# microcontroller.net
KiCad netlist of a schematic drawn in Altium Designer
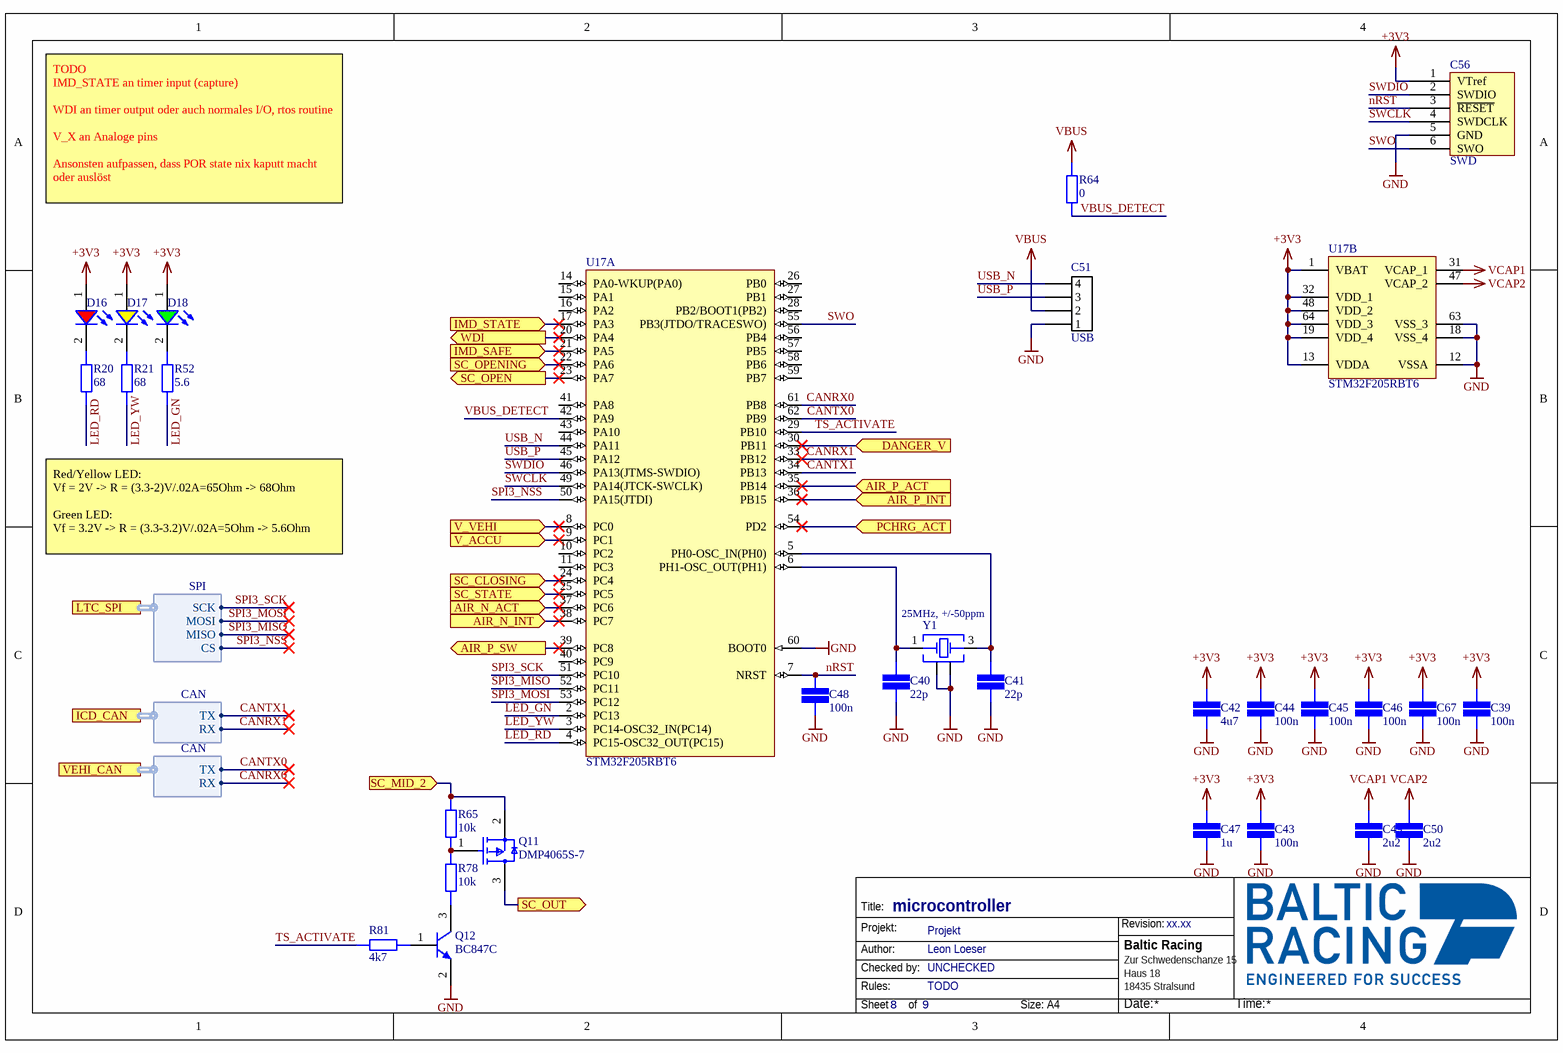
[diagram p0: microcontroller.SchDoc]

(export (version "E")
  (design (tool "Eeschema 10.0.6"))
  (components
    (comp (ref "C39")
      (value "100n")
      (footprint "CAP 0603/1608")
      (description "Capacitor with multiple Footprints")
      (fields (field (name "VOLTAGE") "6.3V") (field (name "Comment") "SMD Capacitor"))
      (libsource (lib "Standardbauteile") (part "SMD Capacitor"))
    )
    (comp (ref "C40")
      (value "22p")
      (footprint "CAP 0603/1608")
      (description "Capacitor with multiple Footprints")
      (fields (field (name "VOLTAGE") "6.3V") (field (name "Comment") "SMD Capacitor"))
      (libsource (lib "") (part "SMD Capacitor_1"))
    )
    (comp (ref "C41")
      (value "22p")
      (footprint "CAP 0603/1608")
      (description "Capacitor with multiple Footprints")
      (fields (field (name "VOLTAGE") "6.3V") (field (name "Comment") "SMD Capacitor"))
      (libsource (lib "") (part "SMD Capacitor_1"))
    )
    (comp (ref "C42")
      (value "4u7")
      (footprint "CAP 0805/2012")
      (description "Capacitor with multiple Footprints")
      (fields (field (name "VOLTAGE") "6.3V") (field (name "Comment") "SMD Capacitor"))
      (libsource (lib "Standardbauteile") (part "SMD Capacitor"))
    )
    (comp (ref "C43")
      (value "100n")
      (footprint "CAP 0603/1608")
      (description "Capacitor with multiple Footprints")
      (fields (field (name "VOLTAGE") "6.3V") (field (name "Comment") "SMD Capacitor"))
      (libsource (lib "Standardbauteile") (part "SMD Capacitor"))
    )
    (comp (ref "C44")
      (value "100n")
      (footprint "CAP 0603/1608")
      (description "Capacitor with multiple Footprints")
      (fields (field (name "VOLTAGE") "6.3V") (field (name "Comment") "SMD Capacitor"))
      (libsource (lib "Standardbauteile") (part "SMD Capacitor"))
    )
    (comp (ref "C45")
      (value "100n")
      (footprint "CAP 0603/1608")
      (description "Capacitor with multiple Footprints")
      (fields (field (name "VOLTAGE") "6.3V") (field (name "Comment") "SMD Capacitor"))
      (libsource (lib "Standardbauteile") (part "SMD Capacitor"))
    )
    (comp (ref "C46")
      (value "100n")
      (footprint "CAP 0603/1608")
      (description "Capacitor with multiple Footprints")
      (fields (field (name "VOLTAGE") "6.3V") (field (name "Comment") "SMD Capacitor"))
      (libsource (lib "Standardbauteile") (part "SMD Capacitor"))
    )
    (comp (ref "C47")
      (value "1u")
      (footprint "CAP 0805/2012")
      (description "Capacitor with multiple Footprints")
      (fields (field (name "VOLTAGE") "6.3V") (field (name "Comment") "SMD Capacitor"))
      (libsource (lib "Standardbauteile") (part "SMD Capacitor"))
    )
    (comp (ref "C48")
      (value "100n")
      (footprint "CAP 0603/1608")
      (description "Capacitor with multiple Footprints")
      (fields (field (name "VOLTAGE") "6.3V") (field (name "Comment") "SMD Capacitor"))
      (libsource (lib "Standardbauteile") (part "SMD Capacitor"))
    )
    (comp (ref "C49")
      (value "2u2")
      (footprint "CAP 0805/2012")
      (description "Capacitor with multiple Footprints")
      (fields (field (name "VOLTAGE") "6.3V") (field (name "Comment") "SMD Capacitor"))
      (libsource (lib "Standardbauteile") (part "SMD Capacitor"))
    )
    (comp (ref "C50")
      (value "2u2")
      (footprint "CAP 0805/2012")
      (description "Capacitor with multiple Footprints")
      (fields (field (name "VOLTAGE") "6.3V") (field (name "Comment") "SMD Capacitor"))
      (libsource (lib "Standardbauteile") (part "SMD Capacitor"))
    )
    (comp (ref "C51")
      (value "USB")
      (footprint "43045-0412")
      (description "Molex Micro-Fit 3.0 4-Pin\r\n600V\r\n8.5V")
      (libsource (lib "Standardbauteile") (part "MicroFit3.0 4-Pin"))
    )
    (comp (ref "C56")
      (value "SWD")
      (footprint "SEGGER_6_PIN")
      (libsource (lib "Standardbauteile") (part "Segger 6-Pin"))
    )
    (comp (ref "C67")
      (value "100n")
      (footprint "CAP 0603/1608")
      (description "Capacitor with multiple Footprints")
      (fields (field (name "VOLTAGE") "6.3V") (field (name "Comment") "SMD Capacitor"))
      (libsource (lib "Standardbauteile") (part "SMD Capacitor"))
    )
    (comp (ref "D16")
      (value "Red, 2 V, 140 deg")
      (footprint "WL-SMCW_0603_H=0.25")
      (description "SMT Mono-color Chip LED Waterclear WL-SMCW, size 0603, Red, 2 V, 140 deg, 100 mcd")
      (fields (field (name "PART NUMBER") "150060RS75020") (field (name "PUBLISHER") "Wurth Elektronik"))
      (libsource (lib "ALTIUM-WL-SMCW-rev18c") (part "150060RS75020"))
    )
    (comp (ref "D17")
      (value "Yellow, 2 V, 140 deg")
      (footprint "WL-SMCW_0603_H=0.25")
      (description "SMT Mono-color Chip LED Waterclear WL-SMCW, size 0603, Yellow, 2 V, 140 deg, 130 mcd")
      (fields (field (name "PART NUMBER") "150060YS75020") (field (name "PUBLISHER") "Wurth Elektronik"))
      (libsource (lib "ALTIUM-WL-SMCW-rev18c") (part "150060YS75020"))
    )
    (comp (ref "D18")
      (value "Green, 3.2 V, 140 deg")
      (footprint "WL-SMCW_0603_H=0.25")
      (description "SMT Mono-color Chip LED Waterclear WL-SMCW, size 0603, Green, 3.2 V, 140 deg, 700 mcd")
      (fields (field (name "PART NUMBER") "150060GS75020") (field (name "PUBLISHER") "Wurth Elektronik"))
      (libsource (lib "ALTIUM-WL-SMCW-rev18c") (part "150060GS75020"))
    )
    (comp (ref "Q11")
      (value "DMP4065S-7")
      (footprint "FP-SOT23-MFG")
      (description "MOSFET P-CH 40V 2.4A SOT23")
      (fields
        (field (name "MANUFACTURER") "Diodes Inc.")
        (field (name "OCTOPART") "https://octopart.com/dmp4065s-7-diodes+inc.-57605044")
      )
      (libsource (lib "Altium Content Vault") (part "90d26376f95f59a583a7107ec0b7fdb"))
    )
    (comp (ref "Q12")
      (value "BC847C")
      (footprint "INF-SOT23_L")
      (description "NPN Silicon AF Transistor, 45 V VCEO, 100 mA IC, SOT23, Reel, Green")
      (fields (field (name "MANUFACTURER") "Infineon"))
      (libsource (lib "Altium Content Vault") (part "INF-BJTNPN-BEC-3"))
    )
    (comp (ref "R20")
      (value "68")
      (footprint "STACKPOLE CSR0603")
      (description "Resistor with multiple footprints")
      (fields (field (name "Comment") "SMD Resistor"))
      (libsource (lib "Standardbauteile") (part "SMD Resistor"))
    )
    (comp (ref "R21")
      (value "68")
      (footprint "STACKPOLE CSR0603")
      (description "Resistor with multiple footprints")
      (fields (field (name "Comment") "SMD Resistor"))
      (libsource (lib "Standardbauteile") (part "SMD Resistor"))
    )
    (comp (ref "R52")
      (value "5.6")
      (footprint "STACKPOLE CSR0603")
      (description "Resistor with multiple footprints")
      (fields (field (name "Comment") "SMD Resistor"))
      (libsource (lib "Standardbauteile") (part "SMD Resistor"))
    )
    (comp (ref "R64")
      (value "0")
      (footprint "STACKPOLE CSR0603")
      (description "Resistor with multiple footprints")
      (fields (field (name "Comment") "SMD Resistor"))
      (libsource (lib "Standardbauteile") (part "SMD Resistor"))
    )
    (comp (ref "R65")
      (value "10k")
      (footprint "STACKPOLE CSR0603")
      (description "Resistor with multiple footprints")
      (fields (field (name "Comment") "SMD Resistor"))
      (libsource (lib "Standardbauteile") (part "SMD Resistor"))
    )
    (comp (ref "R78")
      (value "10k")
      (footprint "STACKPOLE CSR0603")
      (description "Resistor with multiple footprints")
      (fields (field (name "Comment") "SMD Resistor"))
      (libsource (lib "Standardbauteile") (part "SMD Resistor"))
    )
    (comp (ref "R81")
      (value "4k7")
      (footprint "STACKPOLE CSR0603")
      (description "Resistor with multiple footprints")
      (fields (field (name "Comment") "SMD Resistor"))
      (libsource (lib "Standardbauteile") (part "SMD Resistor"))
    )
    (comp (ref "U17")
      (value "STM32F205RBT6")
      (footprint "STM-LQFP64_L")
      (libsource (lib "Altium Content Vault") (part "MC-ARM-STM32F20X-SQ64"))
    )
    (comp (ref "Y1")
      (value "25MHz, +/-50ppm")
      (footprint "WE-XTAL_CFPX-180")
      (description "WE-XTAL Quartz Crystal, SMT, CFPX-180, 25MHz, +/-50ppm")
      (fields (field (name "PART NUMBER") "830035268") (field (name "PUBLISHER") "Wurth Elektronik"))
      (libsource (lib "Altium_WE-XTAL_rev19c") (part "830035268"))
    )
  )
  (nets
    (net (code "3") (name "+3V3") (class "Default")
      (node (ref "C39") (pin "2") (pinfunction "2_2") (pintype "passive"))
      (node (ref "C42") (pin "2") (pinfunction "2_2") (pintype "passive"))
      (node (ref "C43") (pin "2") (pinfunction "2_2") (pintype "passive"))
      (node (ref "C44") (pin "2") (pinfunction "2_2") (pintype "passive"))
      (node (ref "C45") (pin "2") (pinfunction "2_2") (pintype "passive"))
      (node (ref "C46") (pin "2") (pinfunction "2_2") (pintype "passive"))
      (node (ref "C47") (pin "2") (pinfunction "2_2") (pintype "passive"))
      (node (ref "C56") (pin "1") (pinfunction "VTref_1") (pintype "passive"))
      (node (ref "C67") (pin "2") (pinfunction "2_2") (pintype "passive"))
      (node (ref "D16") (pin "1") (pinfunction "A_1") (pintype "passive"))
      (node (ref "D17") (pin "1") (pinfunction "A_1") (pintype "passive"))
      (node (ref "D18") (pin "1") (pinfunction "A_1") (pintype "passive"))
      (node (ref "U17") (pin "1") (pinfunction "VBAT_1") (pintype "power_in"))
      (node (ref "U17") (pin "13") (pinfunction "VDDA_13") (pintype "power_in"))
      (node (ref "U17") (pin "19") (pinfunction "VDD_4_19") (pintype "power_in"))
      (node (ref "U17") (pin "32") (pinfunction "VDD_1_32") (pintype "power_in"))
      (node (ref "U17") (pin "48") (pinfunction "VDD_2_48") (pintype "power_in"))
      (node (ref "U17") (pin "64") (pinfunction "VDD_3_64") (pintype "power_in"))
    )
    (net (code "4") (name "/AIR_N_ACT") (class "Default")
      (node (ref "U17") (pin "37") (pinfunction "PC6_37") (pintype "bidirectional+no_connect"))
    )
    (net (code "5") (name "/AIR_N_INT") (class "Default")
      (node (ref "U17") (pin "38") (pinfunction "PC7_38") (pintype "bidirectional+no_connect"))
    )
    (net (code "6") (name "/AIR_P_ACT") (class "Default")
      (node (ref "U17") (pin "35") (pinfunction "PB14_35") (pintype "bidirectional+no_connect"))
    )
    (net (code "7") (name "/AIR_P_INT") (class "Default")
      (node (ref "U17") (pin "36") (pinfunction "PB15_36") (pintype "bidirectional+no_connect"))
    )
    (net (code "8") (name "/AIR_P_SW") (class "Default")
      (node (ref "U17") (pin "39") (pinfunction "PC8_39") (pintype "bidirectional+no_connect"))
    )
    (net (code "9") (name "/CANRX0") (class "Default")
      (node (ref "U17") (pin "61") (pinfunction "PB8_61") (pintype "bidirectional+no_connect"))
    )
    (net (code "10") (name "/CANRX1") (class "Default")
      (node (ref "U17") (pin "33") (pinfunction "PB12_33") (pintype "bidirectional+no_connect"))
    )
    (net (code "11") (name "/CANTX0") (class "Default")
      (node (ref "U17") (pin "62") (pinfunction "PB9_62") (pintype "bidirectional+no_connect"))
    )
    (net (code "12") (name "/CANTX1") (class "Default")
      (node (ref "U17") (pin "34") (pinfunction "PB13_34") (pintype "bidirectional+no_connect"))
    )
    (net (code "13") (name "/DANGER_V") (class "Default")
      (node (ref "U17") (pin "30") (pinfunction "PB11_30") (pintype "bidirectional+no_connect"))
    )
    (net (code "14") (name "/IMD_SAFE") (class "Default")
      (node (ref "U17") (pin "21") (pinfunction "PA5_21") (pintype "bidirectional+no_connect"))
    )
    (net (code "15") (name "/IMD_STATE") (class "Default")
      (node (ref "U17") (pin "17") (pinfunction "PA3_17") (pintype "bidirectional+no_connect"))
    )
    (net (code "16") (name "/LED_GN") (class "Default")
      (node (ref "R52") (pin "1") (pinfunction "1_1") (pintype "passive"))
      (node (ref "U17") (pin "2") (pinfunction "PC13_2") (pintype "bidirectional"))
    )
    (net (code "17") (name "/LED_RD") (class "Default")
      (node (ref "R20") (pin "1") (pinfunction "1_1") (pintype "passive"))
      (node (ref "U17") (pin "4") (pinfunction "PC15-OSC32_OUT(PC15)_4") (pintype "bidirectional"))
    )
    (net (code "18") (name "/LED_YW") (class "Default")
      (node (ref "R21") (pin "1") (pinfunction "1_1") (pintype "passive"))
      (node (ref "U17") (pin "3") (pinfunction "PC14-OSC32_IN(PC14)_3") (pintype "bidirectional"))
    )
    (net (code "19") (name "/PCHRG_ACT") (class "Default")
      (node (ref "U17") (pin "54") (pinfunction "PD2_54") (pintype "bidirectional+no_connect"))
    )
    (net (code "20") (name "/SC_CLOSING") (class "Default")
      (node (ref "U17") (pin "24") (pinfunction "PC4_24") (pintype "bidirectional+no_connect"))
    )
    (net (code "21") (name "/SC_MID_2") (class "Default")
      (node (ref "Q11") (pin "2") (pinfunction "S_2") (pintype "passive"))
      (node (ref "R65") (pin "1") (pinfunction "1_1") (pintype "passive"))
    )
    (net (code "22") (name "/SC_OPEN") (class "Default")
      (node (ref "U17") (pin "23") (pinfunction "PA7_23") (pintype "bidirectional+no_connect"))
    )
    (net (code "23") (name "/SC_OPENING") (class "Default")
      (node (ref "U17") (pin "22") (pinfunction "PA6_22") (pintype "bidirectional+no_connect"))
    )
    (net (code "24") (name "/SC_OUT") (class "Default")
      (node (ref "Q11") (pin "3") (pinfunction "D_3") (pintype "passive"))
    )
    (net (code "25") (name "/SC_STATE") (class "Default")
      (node (ref "U17") (pin "25") (pinfunction "PC5_25") (pintype "bidirectional+no_connect"))
    )
    (net (code "26") (name "/SPI3_MISO") (class "Default")
      (node (ref "U17") (pin "52") (pinfunction "PC11_52") (pintype "bidirectional+no_connect"))
    )
    (net (code "27") (name "/SPI3_MOSI") (class "Default")
      (node (ref "U17") (pin "53") (pinfunction "PC12_53") (pintype "bidirectional+no_connect"))
    )
    (net (code "28") (name "/SPI3_NSS") (class "Default")
      (node (ref "U17") (pin "50") (pinfunction "PA15(JTDI)_50") (pintype "bidirectional+no_connect"))
    )
    (net (code "29") (name "/SPI3_SCK") (class "Default")
      (node (ref "U17") (pin "51") (pinfunction "PC10_51") (pintype "bidirectional+no_connect"))
    )
    (net (code "30") (name "/SWCLK") (class "Default")
      (node (ref "C56") (pin "4") (pinfunction "SWDCLK_4") (pintype "passive"))
      (node (ref "U17") (pin "49") (pinfunction "PA14(JTCK-SWCLK)_49") (pintype "bidirectional"))
    )
    (net (code "31") (name "/SWDIO") (class "Default")
      (node (ref "C56") (pin "2") (pinfunction "SWDIO_2") (pintype "passive"))
      (node (ref "U17") (pin "46") (pinfunction "PA13(JTMS-SWDIO)_46") (pintype "bidirectional"))
    )
    (net (code "32") (name "/SWO") (class "Default")
      (node (ref "C56") (pin "6") (pinfunction "SWO_6") (pintype "passive"))
      (node (ref "U17") (pin "55") (pinfunction "PB3(JTDO/TRACESWO)_55") (pintype "bidirectional"))
    )
    (net (code "33") (name "/TS_ACTIVATE") (class "Default")
      (node (ref "R81") (pin "2") (pinfunction "2_2") (pintype "passive"))
      (node (ref "U17") (pin "29") (pinfunction "PB10_29") (pintype "bidirectional"))
    )
    (net (code "34") (name "/USB_N") (class "Default")
      (node (ref "C51") (pin "4") (pinfunction "4_4") (pintype "passive"))
      (node (ref "U17") (pin "44") (pinfunction "PA11_44") (pintype "bidirectional"))
    )
    (net (code "35") (name "/USB_P") (class "Default")
      (node (ref "C51") (pin "3") (pinfunction "3_3") (pintype "passive"))
      (node (ref "U17") (pin "45") (pinfunction "PA12_45") (pintype "bidirectional"))
    )
    (net (code "36") (name "/VBUS_DETECT") (class "Default")
      (node (ref "R64") (pin "1") (pinfunction "1_1") (pintype "passive"))
      (node (ref "U17") (pin "42") (pinfunction "PA9_42") (pintype "bidirectional"))
    )
    (net (code "37") (name "/V_ACCU") (class "Default")
      (node (ref "U17") (pin "9") (pinfunction "PC1_9") (pintype "bidirectional+no_connect"))
    )
    (net (code "38") (name "/V_VEHI") (class "Default")
      (node (ref "U17") (pin "8") (pinfunction "PC0_8") (pintype "bidirectional+no_connect"))
    )
    (net (code "39") (name "/WDI") (class "Default")
      (node (ref "U17") (pin "20") (pinfunction "PA4_20") (pintype "bidirectional+no_connect"))
    )
    (net (code "40") (name "/nRST") (class "Default")
      (node (ref "C48") (pin "2") (pinfunction "2_2") (pintype "passive"))
      (node (ref "C56") (pin "3") (pinfunction "~{RESET}_3") (pintype "passive"))
      (node (ref "U17") (pin "7") (pinfunction "NRST_7") (pintype "bidirectional"))
    )
    (net (code "43") (name "GND") (class "Default")
      (node (ref "C39") (pin "1") (pinfunction "1_1") (pintype "passive"))
      (node (ref "C40") (pin "1") (pinfunction "1_1") (pintype "passive"))
      (node (ref "C41") (pin "1") (pinfunction "1_1") (pintype "passive"))
      (node (ref "C42") (pin "1") (pinfunction "1_1") (pintype "passive"))
      (node (ref "C43") (pin "1") (pinfunction "1_1") (pintype "passive"))
      (node (ref "C44") (pin "1") (pinfunction "1_1") (pintype "passive"))
      (node (ref "C45") (pin "1") (pinfunction "1_1") (pintype "passive"))
      (node (ref "C46") (pin "1") (pinfunction "1_1") (pintype "passive"))
      (node (ref "C47") (pin "1") (pinfunction "1_1") (pintype "passive"))
      (node (ref "C48") (pin "1") (pinfunction "1_1") (pintype "passive"))
      (node (ref "C49") (pin "1") (pinfunction "1_1") (pintype "passive"))
      (node (ref "C50") (pin "1") (pinfunction "1_1") (pintype "passive"))
      (node (ref "C51") (pin "1") (pinfunction "1_1") (pintype "passive"))
      (node (ref "C56") (pin "5") (pinfunction "GND_5") (pintype "passive"))
      (node (ref "C67") (pin "1") (pinfunction "1_1") (pintype "passive"))
      (node (ref "Q12") (pin "2") (pinfunction "E_2") (pintype "passive"))
      (node (ref "U17") (pin "12") (pinfunction "VSSA_12") (pintype "power_in"))
      (node (ref "U17") (pin "18") (pinfunction "VSS_4_18") (pintype "power_in"))
      (node (ref "U17") (pin "60") (pinfunction "BOOT0_60") (pintype "input"))
      (node (ref "U17") (pin "63") (pinfunction "VSS_3_63") (pintype "power_in"))
      (node (ref "Y1") (pin "2") (pinfunction "GND_2") (pintype "passive"))
      (node (ref "Y1") (pin "4") (pinfunction "GND_4") (pintype "passive"))
    )
    (net (code "44") (name "Net-(D16-K)") (class "Default")
      (node (ref "D16") (pin "2") (pinfunction "K_2") (pintype "passive"))
      (node (ref "R20") (pin "2") (pinfunction "2_2") (pintype "passive"))
    )
    (net (code "45") (name "Net-(D17-K)") (class "Default")
      (node (ref "D17") (pin "2") (pinfunction "K_2") (pintype "passive"))
      (node (ref "R21") (pin "2") (pinfunction "2_2") (pintype "passive"))
    )
    (net (code "46") (name "Net-(D18-K)") (class "Default")
      (node (ref "D18") (pin "2") (pinfunction "K_2") (pintype "passive"))
      (node (ref "R52") (pin "2") (pinfunction "2_2") (pintype "passive"))
    )
    (net (code "47") (name "Net-(Q11-G)") (class "Default")
      (node (ref "Q11") (pin "1") (pinfunction "G_1") (pintype "passive"))
      (node (ref "R65") (pin "2") (pinfunction "2_2") (pintype "passive"))
      (node (ref "R78") (pin "1") (pinfunction "1_1") (pintype "passive"))
    )
    (net (code "48") (name "Net-(Q12-B)") (class "Default")
      (node (ref "Q12") (pin "1") (pinfunction "B_1") (pintype "passive"))
      (node (ref "R81") (pin "1") (pinfunction "1_1") (pintype "passive"))
    )
    (net (code "49") (name "Net-(Q12-C)") (class "Default")
      (node (ref "Q12") (pin "3") (pinfunction "C_3") (pintype "passive"))
      (node (ref "R78") (pin "2") (pinfunction "2_2") (pintype "passive"))
    )
    (net (code "50") (name "Net-(U17A-PH0-OSC_IN(PH0))") (class "Default")
      (node (ref "C41") (pin "2") (pinfunction "2_2") (pintype "passive"))
      (node (ref "U17") (pin "5") (pinfunction "PH0-OSC_IN(PH0)_5") (pintype "bidirectional"))
      (node (ref "Y1") (pin "3") (pinfunction "Crystal_3") (pintype "passive"))
    )
    (net (code "51") (name "Net-(U17A-PH1-OSC_OUT(PH1))") (class "Default")
      (node (ref "C40") (pin "2") (pinfunction "2_2") (pintype "passive"))
      (node (ref "U17") (pin "6") (pinfunction "PH1-OSC_OUT(PH1)_6") (pintype "bidirectional"))
      (node (ref "Y1") (pin "1") (pinfunction "Crystal_1") (pintype "passive"))
    )
    (net (code "52") (name "VBUS") (class "Default")
      (node (ref "C51") (pin "2") (pinfunction "2_2") (pintype "passive"))
      (node (ref "R64") (pin "2") (pinfunction "2_2") (pintype "passive"))
    )
    (net (code "53") (name "VCAP1") (class "Default")
      (node (ref "C49") (pin "2") (pinfunction "2_2") (pintype "passive"))
      (node (ref "U17") (pin "31") (pinfunction "VCAP_1_31") (pintype "power_in"))
    )
    (net (code "54") (name "VCAP2") (class "Default")
      (node (ref "C50") (pin "2") (pinfunction "2_2") (pintype "passive"))
      (node (ref "U17") (pin "47") (pinfunction "VCAP_2_47") (pintype "power_in"))
    )
    (net (code "55") (name "unconnected-(U17A-PA0-WKUP(PA0)-Pad14)") (class "Default")
      (node (ref "U17") (pin "14") (pinfunction "PA0-WKUP(PA0)_14") (pintype "bidirectional"))
    )
    (net (code "56") (name "unconnected-(U17A-PA1-Pad15)") (class "Default")
      (node (ref "U17") (pin "15") (pinfunction "PA1_15") (pintype "bidirectional"))
    )
    (net (code "57") (name "unconnected-(U17A-PA2-Pad16)") (class "Default")
      (node (ref "U17") (pin "16") (pinfunction "PA2_16") (pintype "bidirectional"))
    )
    (net (code "58") (name "unconnected-(U17A-PA8-Pad41)") (class "Default")
      (node (ref "U17") (pin "41") (pinfunction "PA8_41") (pintype "bidirectional"))
    )
    (net (code "59") (name "unconnected-(U17A-PA10-Pad43)") (class "Default")
      (node (ref "U17") (pin "43") (pinfunction "PA10_43") (pintype "bidirectional"))
    )
    (net (code "60") (name "unconnected-(U17A-PB0-Pad26)") (class "Default")
      (node (ref "U17") (pin "26") (pinfunction "PB0_26") (pintype "bidirectional"))
    )
    (net (code "61") (name "unconnected-(U17A-PB1-Pad27)") (class "Default")
      (node (ref "U17") (pin "27") (pinfunction "PB1_27") (pintype "bidirectional"))
    )
    (net (code "62") (name "unconnected-(U17A-PB2{slash}BOOT1(PB2)-Pad28)") (class "Default")
      (node (ref "U17") (pin "28") (pinfunction "PB2/BOOT1(PB2)_28") (pintype "bidirectional"))
    )
    (net (code "63") (name "unconnected-(U17A-PB4-Pad56)") (class "Default")
      (node (ref "U17") (pin "56") (pinfunction "PB4_56") (pintype "bidirectional"))
    )
    (net (code "64") (name "unconnected-(U17A-PB5-Pad57)") (class "Default")
      (node (ref "U17") (pin "57") (pinfunction "PB5_57") (pintype "bidirectional"))
    )
    (net (code "65") (name "unconnected-(U17A-PB6-Pad58)") (class "Default")
      (node (ref "U17") (pin "58") (pinfunction "PB6_58") (pintype "bidirectional"))
    )
    (net (code "66") (name "unconnected-(U17A-PB7-Pad59)") (class "Default")
      (node (ref "U17") (pin "59") (pinfunction "PB7_59") (pintype "bidirectional"))
    )
    (net (code "67") (name "unconnected-(U17A-PC2-Pad10)") (class "Default")
      (node (ref "U17") (pin "10") (pinfunction "PC2_10") (pintype "bidirectional"))
    )
    (net (code "68") (name "unconnected-(U17A-PC3-Pad11)") (class "Default")
      (node (ref "U17") (pin "11") (pinfunction "PC3_11") (pintype "bidirectional"))
    )
    (net (code "69") (name "unconnected-(U17A-PC9-Pad40)") (class "Default")
      (node (ref "U17") (pin "40") (pinfunction "PC9_40") (pintype "bidirectional"))
    )
  )
)
